# REUN_468349_001_PSU_Board_Logic.net
KiCad netlist of a schematic drawn in Altium Designer
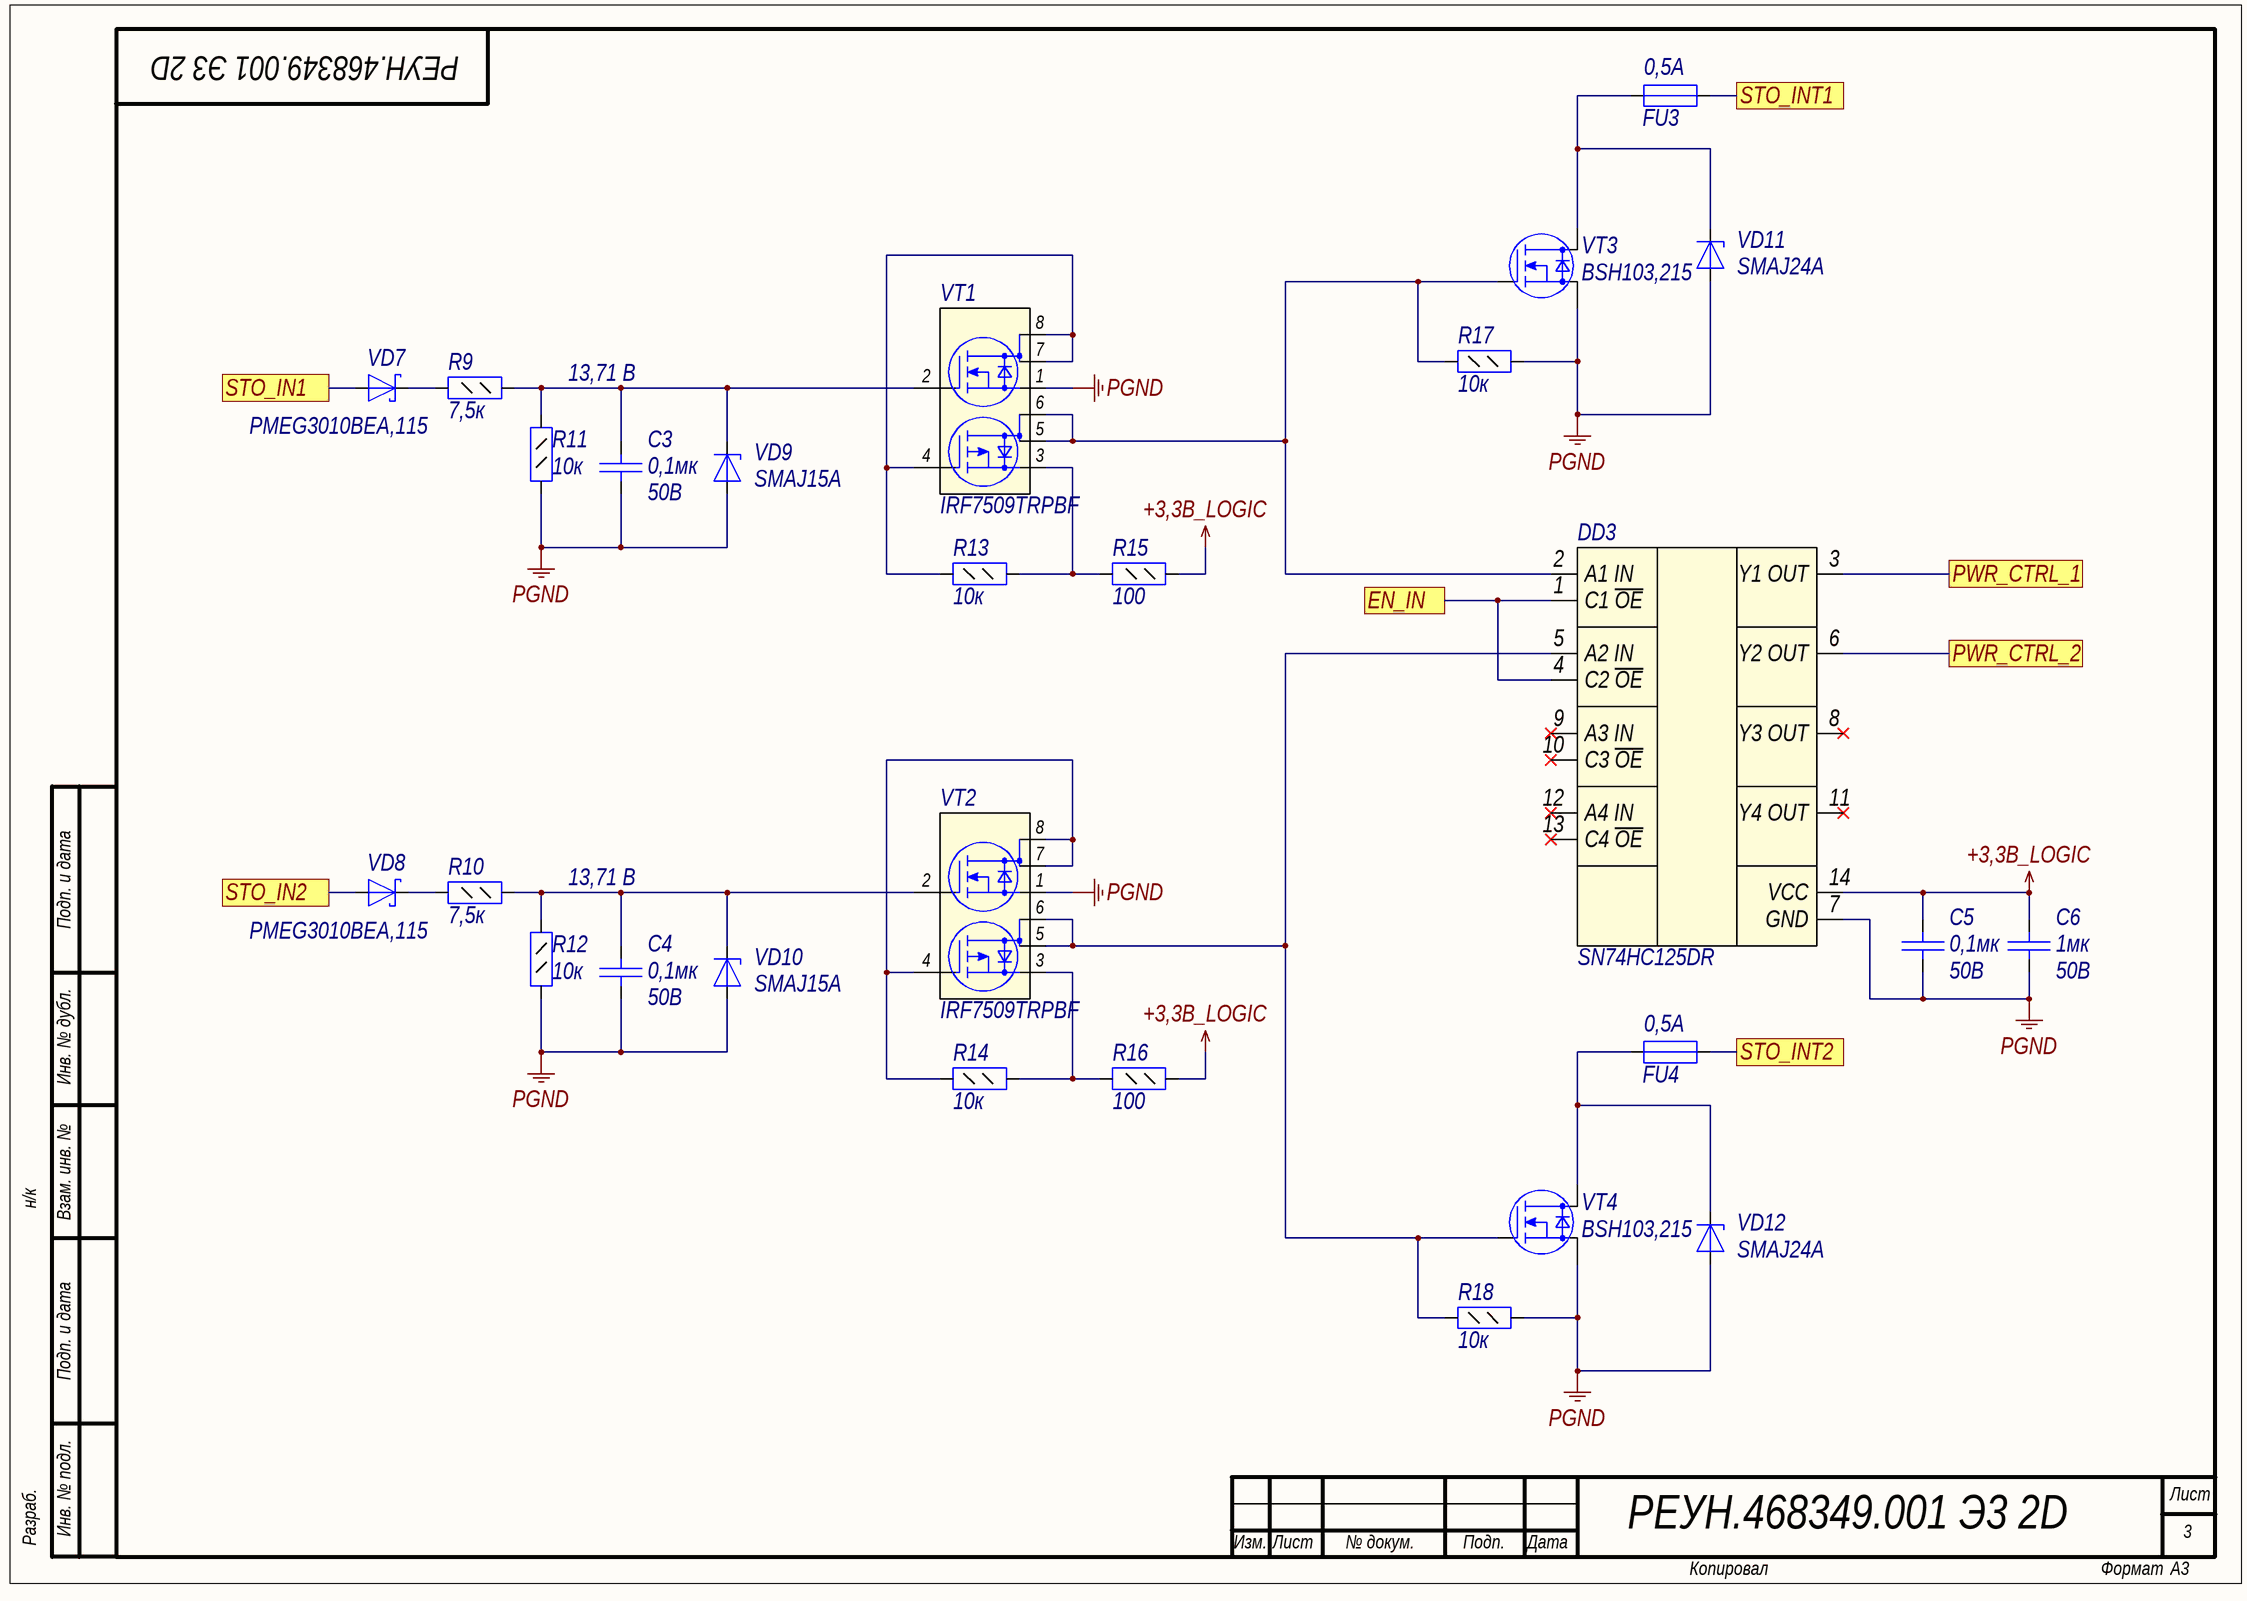
[diagram p0: REUN.468349.001_PSU_Board_Logic.SchDoc]

(export (version "E")
  (design (tool "Eeschema 10.0.6"))
  (components
    (comp (ref "C3")
      (value "0,1мк")
      (footprint "C0805")
      (description "Конденсатор")
      (fields (field (name "VOLTAGE") "50B") (field (name "PART NUMBER") "GRM21BR71H104KA01K"))
      (libsource (lib "MOP44") (part "Capacitor"))
    )
    (comp (ref "C4")
      (value "0,1мк")
      (footprint "C0805")
      (description "Конденсатор")
      (fields (field (name "VOLTAGE") "50B") (field (name "PART NUMBER") "GRM21BR71H104KA01K"))
      (libsource (lib "MOP44") (part "Capacitor"))
    )
    (comp (ref "C5")
      (value "0,1мк")
      (footprint "C0805")
      (description "Конденсатор")
      (fields (field (name "VOLTAGE") "50B") (field (name "PART NUMBER") "GRM21BR71H104KA01K"))
      (libsource (lib "MOP44") (part "Capacitor"))
    )
    (comp (ref "C6")
      (value "1мк")
      (footprint "C0805")
      (description "Конденсатор")
      (fields (field (name "VOLTAGE") "50B") (field (name "PART NUMBER") "GRM21BR71H105KA12L"))
      (libsource (lib "MOP44") (part "Capacitor"))
    )
    (comp (ref "DD3")
      (value "SN74HC125DR")
      (footprint "SO14")
      (description "Quad Tri-State Buffer IC")
      (libsource (lib "MOP44") (part "74HCT125D"))
    )
    (comp (ref "FU3")
      (value "Fuse")
      (footprint "FUSE812")
      (description "Предохранитель")
      (fields (field (name "I HOLD") "0,5A") (field (name "PART NUMBER") "MF-MSMF050"))
      (libsource (lib "MOP44") (part "Fuse"))
    )
    (comp (ref "FU4")
      (value "Fuse")
      (footprint "FUSE812")
      (description "Предохранитель")
      (fields (field (name "I HOLD") "0,5A") (field (name "PART NUMBER") "MF-MSMF050"))
      (libsource (lib "MOP44") (part "Fuse"))
    )
    (comp (ref "R9")
      (value "7,5к")
      (footprint "R0805")
      (description "Резистор")
      (fields (field (name "PART NUMBER") "RC0805FR-077K5") (field (name "POWER") "0,125Вт"))
      (libsource (lib "MOP44") (part "Resistor_0,125Вт"))
    )
    (comp (ref "R10")
      (value "7,5к")
      (footprint "R0805")
      (description "Резистор")
      (fields (field (name "PART NUMBER") "RC0805FR-077K5") (field (name "POWER") "0,125Вт"))
      (libsource (lib "MOP44") (part "Resistor_0,125Вт"))
    )
    (comp (ref "R11")
      (value "10к")
      (footprint "R0805")
      (description "Резистор")
      (fields (field (name "PART NUMBER") "RC0805FR-0710KL") (field (name "POWER") "0,125Вт"))
      (libsource (lib "") (part "Resistor_0,125Вт_2"))
    )
    (comp (ref "R12")
      (value "10к")
      (footprint "R0805")
      (description "Резистор")
      (fields (field (name "PART NUMBER") "RC0805FR-0710KL") (field (name "POWER") "0,125Вт"))
      (libsource (lib "") (part "Resistor_0,125Вт_2"))
    )
    (comp (ref "R13")
      (value "10к")
      (footprint "R0805")
      (description "Резистор")
      (fields (field (name "PART NUMBER") "RC0805FR-0710KL") (field (name "POWER") "0,125Вт"))
      (libsource (lib "") (part "Resistor_0,125Вт_1"))
    )
    (comp (ref "R14")
      (value "10к")
      (footprint "R0805")
      (description "Резистор")
      (fields (field (name "PART NUMBER") "RC0805FR-0710KL") (field (name "POWER") "0,125Вт"))
      (libsource (lib "") (part "Resistor_0,125Вт_1"))
    )
    (comp (ref "R15")
      (value "100")
      (footprint "R0805")
      (description "Резистор")
      (fields (field (name "PART NUMBER") "RC0805FR-07100RL") (field (name "POWER") "0,125Вт"))
      (libsource (lib "MOP44") (part "Resistor_0,125Вт"))
    )
    (comp (ref "R16")
      (value "100")
      (footprint "R0805")
      (description "Резистор")
      (fields (field (name "PART NUMBER") "RC0805FR-07100RL") (field (name "POWER") "0,125Вт"))
      (libsource (lib "MOP44") (part "Resistor_0,125Вт"))
    )
    (comp (ref "R17")
      (value "10к")
      (footprint "R0805")
      (description "Резистор")
      (fields (field (name "PART NUMBER") "RC0805FR-0710KL") (field (name "POWER") "0,125Вт"))
      (libsource (lib "") (part "Resistor_0,125Вт_1"))
    )
    (comp (ref "R18")
      (value "10к")
      (footprint "R0805")
      (description "Резистор")
      (fields (field (name "PART NUMBER") "RC0805FR-0710KL") (field (name "POWER") "0,125Вт"))
      (libsource (lib "") (part "Resistor_0,125Вт_1"))
    )
    (comp (ref "VD7")
      (value "PMEG3010BEA,115")
      (footprint "SOD-323")
      (description "Диод Шоттки")
      (libsource (lib "MOP44") (part "DiodeSchottky"))
    )
    (comp (ref "VD8")
      (value "PMEG3010BEA,115")
      (footprint "SOD-323")
      (description "Диод Шоттки")
      (libsource (lib "MOP44") (part "DiodeSchottky"))
    )
    (comp (ref "VD9")
      (value "SMAJ15A")
      (footprint "SMA")
      (description "Cтабилитрон (лавинный выпрямительный диод) односторонний")
      (libsource (lib "MOP44") (part "DiodeZener"))
    )
    (comp (ref "VD10")
      (value "SMAJ15A")
      (footprint "SMA")
      (description "Cтабилитрон (лавинный выпрямительный диод) односторонний")
      (libsource (lib "MOP44") (part "DiodeZener"))
    )
    (comp (ref "VD11")
      (value "SMAJ24A")
      (footprint "SMA")
      (description "Cтабилитрон (лавинный выпрямительный диод) односторонний")
      (libsource (lib "MOP44") (part "DiodeZener"))
    )
    (comp (ref "VD12")
      (value "SMAJ24A")
      (footprint "SMA")
      (description "Cтабилитрон (лавинный выпрямительный диод) односторонний")
      (libsource (lib "MOP44") (part "DiodeZener"))
    )
    (comp (ref "VT1")
      (value "IRF7509TRPBF")
      (footprint "Micro8")
      (description "Комплементарная сборка МОП")
      (fields (field (name "MANUFACTURER") "International Rectifier"))
      (libsource (lib "MOP44") (part "IRF7509TRPBF"))
    )
    (comp (ref "VT2")
      (value "IRF7509TRPBF")
      (footprint "Micro8")
      (description "Комплементарная сборка МОП")
      (fields (field (name "MANUFACTURER") "International Rectifier"))
      (libsource (lib "MOP44") (part "IRF7509TRPBF"))
    )
    (comp (ref "VT3")
      (value "BSH103,215")
      (footprint "SOT23-3")
      (description "N-MOSFET")
      (fields (field (name "MANUFACTURER") "Nexperia"))
      (libsource (lib "REUN.468349.001_PSU_Board") (part "mosfert36"))
    )
    (comp (ref "VT4")
      (value "BSH103,215")
      (footprint "SOT23-3")
      (description "N-MOSFET")
      (fields (field (name "MANUFACTURER") "Nexperia"))
      (libsource (lib "REUN.468349.001_PSU_Board") (part "mosfert36"))
    )
  )
  (nets
    (net (code "1") (name "+3,3B_LOGIC") (class "Default")
      (node (ref "C5") (pin "2") (pinfunction "2_2") (pintype "passive"))
      (node (ref "C6") (pin "2") (pinfunction "2_2") (pintype "passive"))
      (node (ref "DD3") (pin "14") (pinfunction "VCC_14") (pintype "power_in"))
      (node (ref "R15") (pin "1") (pinfunction "1_1") (pintype "passive"))
      (node (ref "R16") (pin "1") (pinfunction "1_1") (pintype "passive"))
    )
    (net (code "2") (name "/EN_IN") (class "Default")
      (node (ref "DD3") (pin "1") (pinfunction "C1_~{OE}_1") (pintype "power_in"))
      (node (ref "DD3") (pin "4") (pinfunction "C2_~{OE}_4") (pintype "power_in"))
    )
    (net (code "3") (name "/PWR_CTRL_1") (class "Default")
      (node (ref "DD3") (pin "3") (pinfunction "Y1_OUT_3") (pintype "power_in"))
    )
    (net (code "4") (name "/PWR_CTRL_2") (class "Default")
      (node (ref "DD3") (pin "6") (pinfunction "Y2_OUT_6") (pintype "power_in"))
    )
    (net (code "5") (name "/STO_IN1") (class "Default")
      (node (ref "VD7") (pin "2") (pinfunction "A_2") (pintype "passive"))
    )
    (net (code "6") (name "/STO_IN2") (class "Default")
      (node (ref "VD8") (pin "2") (pinfunction "A_2") (pintype "passive"))
    )
    (net (code "7") (name "/STO_INT1") (class "Default")
      (node (ref "FU3") (pin "2") (pinfunction "2_2") (pintype "passive"))
    )
    (net (code "8") (name "/STO_INT2") (class "Default")
      (node (ref "FU4") (pin "2") (pinfunction "2_2") (pintype "passive"))
    )
    (net (code "9") (name "Net-(DD3-A1_IN)") (class "Default")
      (node (ref "DD3") (pin "2") (pinfunction "A1_IN_2") (pintype "power_in"))
      (node (ref "R17") (pin "1") (pinfunction "1_1") (pintype "passive"))
      (node (ref "VT1") (pin "5") (pinfunction "D2_5") (pintype "passive"))
      (node (ref "VT1") (pin "6") (pinfunction "D2_6") (pintype "passive"))
      (node (ref "VT3") (pin "1") (pinfunction "G_1") (pintype "passive"))
    )
    (net (code "10") (name "Net-(DD3-A2_IN)") (class "Default")
      (node (ref "DD3") (pin "5") (pinfunction "A2_IN_5") (pintype "power_in"))
      (node (ref "R18") (pin "1") (pinfunction "1_1") (pintype "passive"))
      (node (ref "VT2") (pin "5") (pinfunction "D2_5") (pintype "passive"))
      (node (ref "VT2") (pin "6") (pinfunction "D2_6") (pintype "passive"))
      (node (ref "VT4") (pin "1") (pinfunction "G_1") (pintype "passive"))
    )
    (net (code "11") (name "Net-(VD7-K)") (class "Default")
      (node (ref "R9") (pin "2") (pinfunction "2_2") (pintype "passive"))
      (node (ref "VD7") (pin "1") (pinfunction "K_1") (pintype "passive"))
    )
    (net (code "12") (name "Net-(VD8-K)") (class "Default")
      (node (ref "R10") (pin "2") (pinfunction "2_2") (pintype "passive"))
      (node (ref "VD8") (pin "1") (pinfunction "K_1") (pintype "passive"))
    )
    (net (code "13") (name "Net-(VD9-K)") (class "Default")
      (node (ref "C3") (pin "2") (pinfunction "2_2") (pintype "passive"))
      (node (ref "R11") (pin "1") (pinfunction "1_1") (pintype "passive"))
      (node (ref "R9") (pin "1") (pinfunction "1_1") (pintype "passive"))
      (node (ref "VD9") (pin "1") (pinfunction "K_1") (pintype "passive"))
      (node (ref "VT1") (pin "2") (pinfunction "G1_2") (pintype "passive"))
    )
    (net (code "14") (name "Net-(VD10-K)") (class "Default")
      (node (ref "C4") (pin "2") (pinfunction "2_2") (pintype "passive"))
      (node (ref "R10") (pin "1") (pinfunction "1_1") (pintype "passive"))
      (node (ref "R12") (pin "1") (pinfunction "1_1") (pintype "passive"))
      (node (ref "VD10") (pin "1") (pinfunction "K_1") (pintype "passive"))
      (node (ref "VT2") (pin "2") (pinfunction "G1_2") (pintype "passive"))
    )
    (net (code "15") (name "Net-(VD11-K)") (class "Default")
      (node (ref "FU3") (pin "1") (pinfunction "1_1") (pintype "passive"))
      (node (ref "VD11") (pin "1") (pinfunction "K_1") (pintype "passive"))
      (node (ref "VT3") (pin "3") (pinfunction "D_3") (pintype "passive"))
    )
    (net (code "16") (name "Net-(VD12-K)") (class "Default")
      (node (ref "FU4") (pin "1") (pinfunction "1_1") (pintype "passive"))
      (node (ref "VD12") (pin "1") (pinfunction "K_1") (pintype "passive"))
      (node (ref "VT4") (pin "3") (pinfunction "D_3") (pintype "passive"))
    )
    (net (code "17") (name "Net-(VT1-G2)") (class "Default")
      (node (ref "R13") (pin "1") (pinfunction "1_1") (pintype "passive"))
      (node (ref "VT1") (pin "4") (pinfunction "G2_4") (pintype "passive"))
      (node (ref "VT1") (pin "7") (pinfunction "D1_7") (pintype "passive"))
      (node (ref "VT1") (pin "8") (pinfunction "D1_8") (pintype "passive"))
    )
    (net (code "18") (name "Net-(VT1-S2)") (class "Default")
      (node (ref "R13") (pin "2") (pinfunction "2_2") (pintype "passive"))
      (node (ref "R15") (pin "2") (pinfunction "2_2") (pintype "passive"))
      (node (ref "VT1") (pin "3") (pinfunction "S2_3") (pintype "passive"))
    )
    (net (code "19") (name "Net-(VT2-G2)") (class "Default")
      (node (ref "R14") (pin "1") (pinfunction "1_1") (pintype "passive"))
      (node (ref "VT2") (pin "4") (pinfunction "G2_4") (pintype "passive"))
      (node (ref "VT2") (pin "7") (pinfunction "D1_7") (pintype "passive"))
      (node (ref "VT2") (pin "8") (pinfunction "D1_8") (pintype "passive"))
    )
    (net (code "20") (name "Net-(VT2-S2)") (class "Default")
      (node (ref "R14") (pin "2") (pinfunction "2_2") (pintype "passive"))
      (node (ref "R16") (pin "2") (pinfunction "2_2") (pintype "passive"))
      (node (ref "VT2") (pin "3") (pinfunction "S2_3") (pintype "passive"))
    )
    (net (code "21") (name "PGND") (class "Default")
      (node (ref "C3") (pin "1") (pinfunction "1_1") (pintype "passive"))
      (node (ref "C4") (pin "1") (pinfunction "1_1") (pintype "passive"))
      (node (ref "C5") (pin "1") (pinfunction "1_1") (pintype "passive"))
      (node (ref "C6") (pin "1") (pinfunction "1_1") (pintype "passive"))
      (node (ref "DD3") (pin "7") (pinfunction "GND_7") (pintype "power_in"))
      (node (ref "R11") (pin "2") (pinfunction "2_2") (pintype "passive"))
      (node (ref "R12") (pin "2") (pinfunction "2_2") (pintype "passive"))
      (node (ref "R17") (pin "2") (pinfunction "2_2") (pintype "passive"))
      (node (ref "R18") (pin "2") (pinfunction "2_2") (pintype "passive"))
      (node (ref "VD10") (pin "2") (pinfunction "A_2") (pintype "passive"))
      (node (ref "VD11") (pin "2") (pinfunction "A_2") (pintype "passive"))
      (node (ref "VD12") (pin "2") (pinfunction "A_2") (pintype "passive"))
      (node (ref "VD9") (pin "2") (pinfunction "A_2") (pintype "passive"))
      (node (ref "VT1") (pin "1") (pinfunction "S1_1") (pintype "passive"))
      (node (ref "VT2") (pin "1") (pinfunction "S1_1") (pintype "passive"))
      (node (ref "VT3") (pin "2") (pinfunction "S_2") (pintype "passive"))
      (node (ref "VT4") (pin "2") (pinfunction "S_2") (pintype "passive"))
    )
    (net (code "22") (name "unconnected-(DD3-A3_IN-Pad9)") (class "Default")
      (node (ref "DD3") (pin "9") (pinfunction "A3_IN_9") (pintype "power_in+no_connect"))
    )
    (net (code "23") (name "unconnected-(DD3-A4_IN-Pad12)") (class "Default")
      (node (ref "DD3") (pin "12") (pinfunction "A4_IN_12") (pintype "power_in+no_connect"))
    )
    (net (code "24") (name "unconnected-(DD3-C3_~{OE}-Pad10)") (class "Default")
      (node (ref "DD3") (pin "10") (pinfunction "C3_~{OE}_10") (pintype "power_in+no_connect"))
    )
    (net (code "25") (name "unconnected-(DD3-C4_~{OE}-Pad13)") (class "Default")
      (node (ref "DD3") (pin "13") (pinfunction "C4_~{OE}_13") (pintype "power_in+no_connect"))
    )
    (net (code "26") (name "unconnected-(DD3-Y3_OUT-Pad8)") (class "Default")
      (node (ref "DD3") (pin "8") (pinfunction "Y3_OUT_8") (pintype "power_in+no_connect"))
    )
    (net (code "27") (name "unconnected-(DD3-Y4_OUT-Pad11)") (class "Default")
      (node (ref "DD3") (pin "11") (pinfunction "Y4_OUT_11") (pintype "power_in+no_connect"))
    )
  )
)
